# Sheet5.net
KiCad netlist of a schematic drawn in Altium Designer
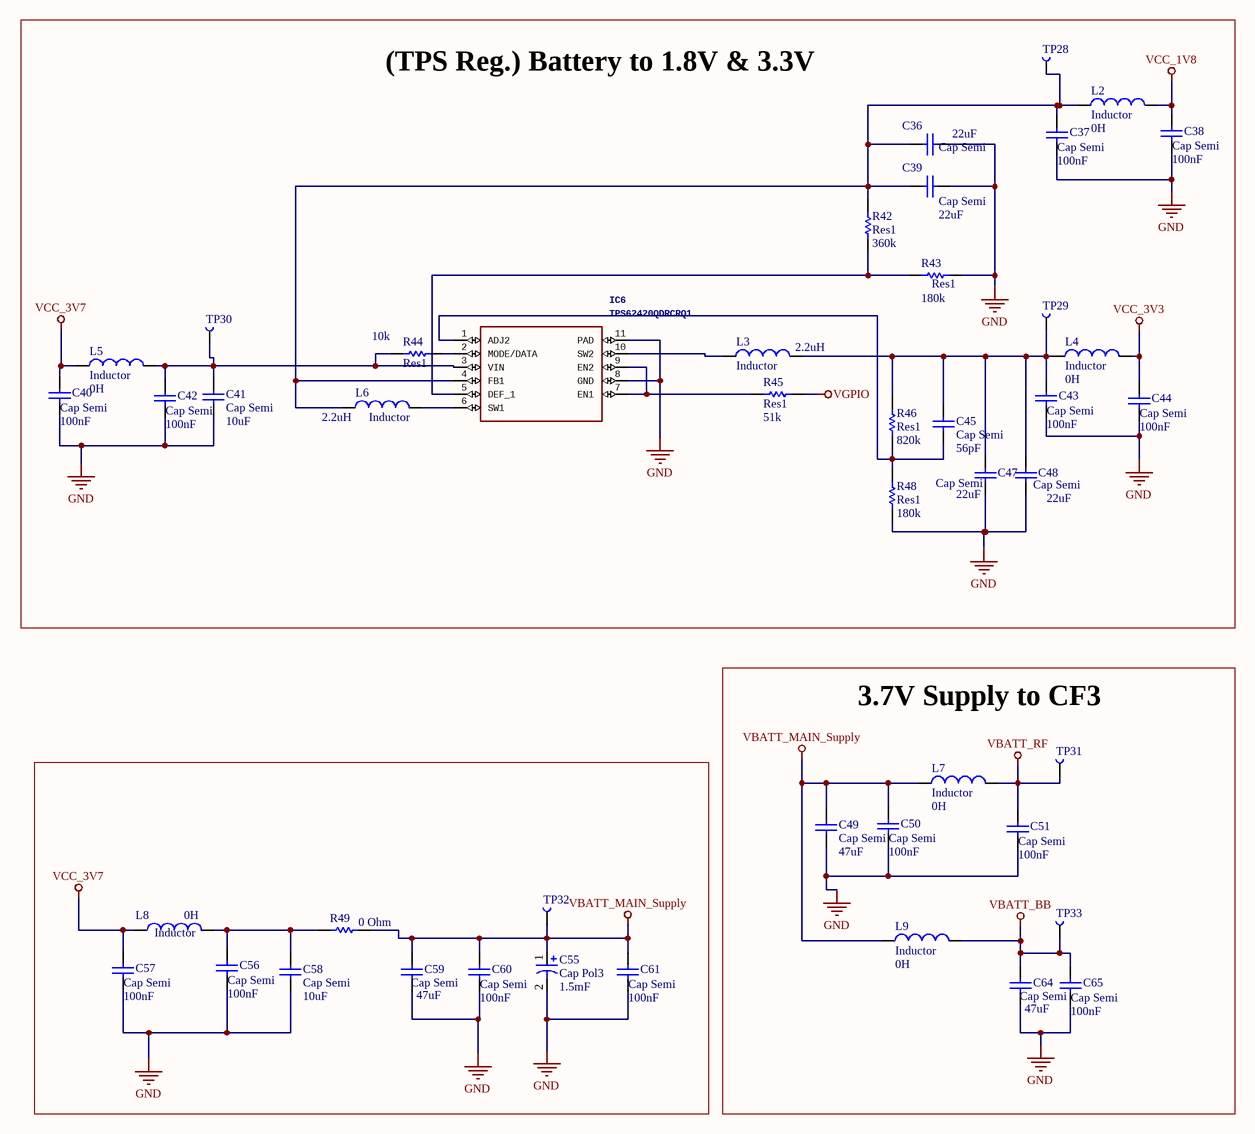
[diagram p0: Sheet5.SchDoc]

(export (version "E")
  (design (tool "Eeschema 10.0.6"))
  (components
    (comp (ref "C36")
      (value "Cap Semi")
      (footprint "CAP 0603/1608")
      (description "22µF ±20% 6.3V Ceramic Capacitor X5R 0603 (1608 Metric)")
      (fields
        (field (name "PART NUMBER") "GRM188R60J226MEA0D")
        (field (name "ALTIUM_VALUE") "22uF")
        (field (name "PUBLISHER") "Altium Limited")
      )
      (libsource (lib "Miscellaneous Devices") (part "Cap Semi"))
    )
    (comp (ref "C37")
      (value "Cap Semi")
      (footprint "CAP 0402/1005")
      (description "0.1µF ±10% 10V Ceramic Capacitor X5R 0402 (1005 Metric)")
      (fields (field (name "PART NUMBER") "LMK105BJ104KV-F") (field (name "ALTIUM_VALUE") "100nF"))
      (libsource (lib "Miscellaneous Devices") (part "Cap Semi"))
    )
    (comp (ref "C38")
      (value "Cap Semi")
      (footprint "CAP 0402/1005")
      (description "0.1µF ±10% 10V Ceramic Capacitor X5R 0402 (1005 Metric)")
      (fields (field (name "PART NUMBER") "LMK105BJ104KV-F") (field (name "ALTIUM_VALUE") "100nF"))
      (libsource (lib "Miscellaneous Devices") (part "Cap Semi"))
    )
    (comp (ref "C39")
      (value "Cap Semi")
      (footprint "CAP 0603/1608")
      (description "22µF ±20% 6.3V Ceramic Capacitor X5R 0603 (1608 Metric)")
      (fields
        (field (name "PART NUMBER") "GRM188R60J226MEA0D")
        (field (name "ALTIUM_VALUE") "22uF")
        (field (name "PUBLISHER") "Altium Limited")
      )
      (libsource (lib "Miscellaneous Devices") (part "Cap Semi"))
    )
    (comp (ref "C40")
      (value "Cap Semi")
      (footprint "CAP 0402/1005")
      (description "0.1µF -20%, +80% 16V Ceramic Capacitor Y5V (F) 0402 (1005 Metric)")
      (fields (field (name "PART NUMBER") "VJ0402V104ZXJCW1BC") (field (name "ALTIUM_VALUE") "100nF"))
      (libsource (lib "Miscellaneous Devices") (part "Cap Semi"))
    )
    (comp (ref "C41")
      (value "Cap Semi")
      (footprint "CAP 0805/2012")
      (description "10µF ±10% 10V Ceramic Capacitor X5R 0805 (2012 Metric)")
      (fields
        (field (name "PART NUMBER") "LMK212BJ106KG-T")
        (field (name "ALTIUM_VALUE") "10uF")
        (field (name "PUBLISHER") "Altium Limited")
      )
      (libsource (lib "Miscellaneous Devices") (part "Cap Semi"))
    )
    (comp (ref "C42")
      (value "Cap Semi")
      (footprint "CAP 0402/1005")
      (description "0.1µF -20%, +80% 16V Ceramic Capacitor Y5V (F) 0402 (1005 Metric)")
      (fields (field (name "PART NUMBER") "VJ0402V104ZXJCW1BC") (field (name "ALTIUM_VALUE") "100nF"))
      (libsource (lib "Miscellaneous Devices") (part "Cap Semi"))
    )
    (comp (ref "C43")
      (value "Cap Semi")
      (footprint "CAP 0402/1005")
      (description "0.1µF ±10% 10V Ceramic Capacitor X5R 0402 (1005 Metric)")
      (fields (field (name "PART NUMBER") "LMK105BJ104KV-F") (field (name "ALTIUM_VALUE") "100nF"))
      (libsource (lib "Miscellaneous Devices") (part "Cap Semi"))
    )
    (comp (ref "C44")
      (value "Cap Semi")
      (footprint "CAP 0402/1005")
      (description "0.1µF ±10% 10V Ceramic Capacitor X5R 0402 (1005 Metric)")
      (fields (field (name "PART NUMBER") "LMK105BJ104KV-F") (field (name "ALTIUM_VALUE") "100nF"))
      (libsource (lib "Miscellaneous Devices") (part "Cap Semi"))
    )
    (comp (ref "C45")
      (value "Cap Semi")
      (footprint "CAP 0402/1005")
      (description "56pF ±5% 50V Ceramic Capacitor C0G, NP0 0402 (1005 Metric)")
      (fields
        (field (name "PART NUMBER") "UMK105CG560JV-F")
        (field (name "ALTIUM_VALUE") "56pF")
        (field (name "PUBLISHER") "Altium Limited")
      )
      (libsource (lib "Miscellaneous Devices") (part "Cap Semi"))
    )
    (comp (ref "C47")
      (value "Cap Semi")
      (footprint "CAP 0603/1608")
      (description "22µF ±20% 6.3V Ceramic Capacitor X5R 0603 (1608 Metric)")
      (fields
        (field (name "PART NUMBER") "GRM188R60J226MEA0D")
        (field (name "ALTIUM_VALUE") "22uF")
        (field (name "PUBLISHER") "Altium Limited")
      )
      (libsource (lib "Miscellaneous Devices") (part "Cap Semi"))
    )
    (comp (ref "C48")
      (value "Cap Semi")
      (footprint "CAP 0603/1608")
      (description "22µF ±20% 6.3V Ceramic Capacitor X5R 0603 (1608 Metric)")
      (fields
        (field (name "PART NUMBER") "GRM188R60J226MEA0D")
        (field (name "ALTIUM_VALUE") "22uF")
        (field (name "PUBLISHER") "Altium Limited")
      )
      (libsource (lib "Miscellaneous Devices") (part "Cap Semi"))
    )
    (comp (ref "C49")
      (value "Cap Semi")
      (footprint "CAP 1206/3216")
      (description "47µF ±20% 10V Ceramic Capacitor X5R 1206 (3216 Metric)")
      (fields
        (field (name "PART NUMBER") "LMK316BJ476ML-T")
        (field (name "ALTIUM_VALUE") "47uF")
        (field (name "PUBLISHER") "Altium Limited")
      )
      (libsource (lib "Miscellaneous Devices") (part "Cap Semi"))
    )
    (comp (ref "C50")
      (value "Cap Semi")
      (footprint "CAP 0402/1005")
      (description "0.1µF ±10% 10V Ceramic Capacitor X5R 0402 (1005 Metric)")
      (fields (field (name "PART NUMBER") "LMK105BJ104KV-F") (field (name "ALTIUM_VALUE") "100nF"))
      (libsource (lib "Miscellaneous Devices") (part "Cap Semi"))
    )
    (comp (ref "C51")
      (value "Cap Semi")
      (footprint "CAP 0402/1005")
      (description "0.1µF ±10% 10V Ceramic Capacitor X5R 0402 (1005 Metric)")
      (fields (field (name "PART NUMBER") "LMK105BJ104KV-F") (field (name "ALTIUM_VALUE") "100nF"))
      (libsource (lib "Miscellaneous Devices") (part "Cap Semi"))
    )
    (comp (ref "C55")
      (value "Cap Pol3")
      (footprint "F720J158MMC")
      (description "1500µF Conformal Coated Tantalum Capacitors 6.3V 2824 (7260 Metric) 140 mOhm")
      (fields
        (field (name "ALTIUM_VALUE") "1.5mF")
        (field (name "PART NUMBER") "F720J158MMC")
        (field (name "PUBLISHER") "Altium Limited")
      )
      (libsource (lib "Miscellaneous Devices") (part "Cap Pol3"))
    )
    (comp (ref "C56")
      (value "Cap Semi")
      (footprint "CAP 0402/1005")
      (description "0.1µF -20%, +80% 16V Ceramic Capacitor Y5V (F) 0402 (1005 Metric)")
      (fields (field (name "PART NUMBER") "VJ0402V104ZXJCW1BC") (field (name "ALTIUM_VALUE") "100nF"))
      (libsource (lib "Miscellaneous Devices") (part "Cap Semi"))
    )
    (comp (ref "C57")
      (value "Cap Semi")
      (footprint "CAP 0402/1005")
      (description "0.1µF -20%, +80% 16V Ceramic Capacitor Y5V (F) 0402 (1005 Metric)")
      (fields (field (name "PART NUMBER") "VJ0402V104ZXJCW1BC") (field (name "ALTIUM_VALUE") "100nF"))
      (libsource (lib "Miscellaneous Devices") (part "Cap Semi"))
    )
    (comp (ref "C58")
      (value "Cap Semi")
      (footprint "CAP 0603/1608")
      (description "10µF ±20% 10V Ceramic Capacitor X5R 0603 (1608 Metric)")
      (fields
        (field (name "PART NUMBER") "GRM188R61A106ME69D")
        (field (name "ALTIUM_VALUE") "10uF")
        (field (name "PUBLISHER") "Altium Limited")
      )
      (libsource (lib "Miscellaneous Devices") (part "Cap Semi"))
    )
    (comp (ref "C59")
      (value "Cap Semi")
      (footprint "CAP 1206/3216")
      (description "47µF ±20% 10V Ceramic Capacitor X5R 1206 (3216 Metric)")
      (fields
        (field (name "PART NUMBER") "LMK316BJ476ML-T")
        (field (name "ALTIUM_VALUE") "47uF")
        (field (name "PUBLISHER") "Altium Limited")
      )
      (libsource (lib "Miscellaneous Devices") (part "Cap Semi"))
    )
    (comp (ref "C60")
      (value "Cap Semi")
      (footprint "CAP 0402/1005")
      (description "0.1µF ±10% 10V Ceramic Capacitor X5R 0402 (1005 Metric)")
      (fields (field (name "PART NUMBER") "LMK105BJ104KV-F") (field (name "ALTIUM_VALUE") "100nF"))
      (libsource (lib "Miscellaneous Devices") (part "Cap Semi"))
    )
    (comp (ref "C61")
      (value "Cap Semi")
      (footprint "CAP 0402/1005")
      (description "0.1µF ±10% 10V Ceramic Capacitor X5R 0402 (1005 Metric)")
      (fields (field (name "PART NUMBER") "LMK105BJ104KV-F") (field (name "ALTIUM_VALUE") "100nF"))
      (libsource (lib "Miscellaneous Devices") (part "Cap Semi"))
    )
    (comp (ref "C64")
      (value "Cap Semi")
      (footprint "CAP 1206/3216")
      (description "47µF ±20% 10V Ceramic Capacitor X5R 1206 (3216 Metric)")
      (fields
        (field (name "PART NUMBER") "LMK316BJ476ML-T")
        (field (name "ALTIUM_VALUE") "47uF")
        (field (name "PUBLISHER") "Altium Limited")
      )
      (libsource (lib "Miscellaneous Devices") (part "Cap Semi"))
    )
    (comp (ref "C65")
      (value "Cap Semi")
      (footprint "CAP 0402/1005")
      (description "0.1µF ±10% 10V Ceramic Capacitor X5R 0402 (1005 Metric)")
      (fields (field (name "PART NUMBER") "LMK105BJ104KV-F") (field (name "ALTIUM_VALUE") "100nF"))
      (libsource (lib "Miscellaneous Devices") (part "Cap Semi"))
    )
    (comp (ref "IC6")
      (value "TPS62420QDRCRQ1")
      (footprint "SON50P300X300X100-11N - 3D")
      (description "Buck Switching Regulator IC Positive Adjustable 0.6V 2 Output 600mA, 1A 10-VFDFN Exposed Pad")
      (fields (field (name "PART NUMBER") "TPS62420DRCR"))
      (libsource (lib "TPS62420QDRCRQ1") (part "TPS62420QDRCRQ1"))
    )
    (comp (ref "L2")
      (value "Inductor")
      (footprint "INDC1608L")
      (description "220 Ohms @ 100MHz 1 Power Line Ferrite Bead 0603 (1608 Metric) 2.2A 50 mOhm")
      (fields
        (field (name "ALTIUM_VALUE") "0H")
        (field (name "PART NUMBER") "MPZ1608S221ATA00")
        (field (name "PUBLISHER") "Altium Limited")
      )
      (libsource (lib "Miscellaneous Devices") (part "Inductor"))
    )
    (comp (ref "L3")
      (value "Inductor")
      (footprint "0402-A")
      (fields
        (field (name "ALTIUM_VALUE") "2.2uH")
        (field (name "PART NUMBER") "MIPF2016D2R2")
        (field (name "PUBLISHER") "Altium Limited")
      )
      (libsource (lib "Miscellaneous Devices") (part "Inductor"))
    )
    (comp (ref "L4")
      (value "Inductor")
      (footprint "INDC1608L")
      (description "220 Ohms @ 100MHz 1 Power Line Ferrite Bead 0603 (1608 Metric) 2.2A 50 mOhm")
      (fields
        (field (name "ALTIUM_VALUE") "0H")
        (field (name "PART NUMBER") "MPZ1608S221ATA00")
        (field (name "PUBLISHER") "Altium Limited")
      )
      (libsource (lib "Miscellaneous Devices") (part "Inductor"))
    )
    (comp (ref "L5")
      (value "Inductor")
      (footprint "INDC1608L")
      (description "220 Ohms @ 100MHz 1 Power Line Ferrite Bead 0603 (1608 Metric) 2.2A 50 mOhm")
      (fields
        (field (name "ALTIUM_VALUE") "0H")
        (field (name "PART NUMBER") "MPZ1608S221ATA00")
        (field (name "PUBLISHER") "Altium Limited")
      )
      (libsource (lib "Miscellaneous Devices") (part "Inductor"))
    )
    (comp (ref "L6")
      (value "Inductor")
      (footprint "0402-A")
      (fields
        (field (name "ALTIUM_VALUE") "2.2uH")
        (field (name "PART NUMBER") "MIPF2016D2R2")
        (field (name "PUBLISHER") "Altium Limited")
      )
      (libsource (lib "Miscellaneous Devices") (part "Inductor"))
    )
    (comp (ref "L7")
      (value "Inductor")
      (footprint "INDC1608L")
      (description "120 Ohms @ 100MHz 1 Power Line Ferrite Bead 0603 (1608 Metric) 2.7A 35 mOhm")
      (fields
        (field (name "ALTIUM_VALUE") "0H")
        (field (name "PART NUMBER") "BKP1608HS121-T")
        (field (name "PUBLISHER") "Altium Limited")
      )
      (libsource (lib "Miscellaneous Devices") (part "Inductor"))
    )
    (comp (ref "L8")
      (value "Inductor")
      (footprint "INDC1608L")
      (description "120 Ohms @ 100MHz 1 Power Line Ferrite Bead 0603 (1608 Metric) 2.7A 35 mOhm")
      (fields
        (field (name "ALTIUM_VALUE") "0H")
        (field (name "PART NUMBER") "BKP1608HS121-T")
        (field (name "PUBLISHER") "Altium Limited")
      )
      (libsource (lib "Miscellaneous Devices") (part "Inductor"))
    )
    (comp (ref "L9")
      (value "Inductor")
      (footprint "INDC1608L")
      (description "120 Ohms @ 100MHz 1 Power Line Ferrite Bead 0603 (1608 Metric) 2.7A 35 mOhm")
      (fields
        (field (name "ALTIUM_VALUE") "0H")
        (field (name "PART NUMBER") "BKP1608HS121-T")
        (field (name "PUBLISHER") "Altium Limited")
      )
      (libsource (lib "Miscellaneous Devices") (part "Inductor"))
    )
    (comp (ref "R42")
      (value "Res1")
      (footprint "RES 0402/1005")
      (description "360 kOhms ±1% 0.063W, 1/16W Chip Resistor 0402 (1005 Metric) Automotive AEC-Q200 Thick Film")
      (fields (field (name "PART NUMBER") "MCR01MZPF3603") (field (name "ALTIUM_VALUE") "360k"))
      (libsource (lib "Miscellaneous Devices") (part "Res1"))
    )
    (comp (ref "R43")
      (value "Res1")
      (footprint "RES 0402/1005")
      (description "180 kOhms ±1% 0.1W, 1/10W Chip Resistor 0402 (1005 Metric) Automotive AEC-Q200 Thick Film")
      (fields (field (name "PART NUMBER") "RK73H1ETTP1803F") (field (name "ALTIUM_VALUE") "180k"))
      (libsource (lib "Miscellaneous Devices") (part "Res1"))
    )
    (comp (ref "R44")
      (value "Res1")
      (footprint "RES 0402/1005")
      (description "10 kOhms ±5% 0.063W, 1/16W Chip Resistor 0402 (1005 Metric) Automotive AEC-Q200 Thick Film")
      (fields (field (name "PART NUMBER") "MCR01MZPJ103") (field (name "ALTIUM_VALUE") "10k"))
      (libsource (lib "Miscellaneous Devices") (part "Res1"))
    )
    (comp (ref "R45")
      (value "Res1")
      (footprint "RES 0402/1005")
      (description "51 kOhms ±5% 0.063W, 1/16W Chip Resistor 0402 (1005 Metric)")
      (fields (field (name "PART NUMBER") "MCR01MZPJ513") (field (name "ALTIUM_VALUE") "51k"))
      (libsource (lib "Miscellaneous Devices") (part "Res1"))
    )
    (comp (ref "R46")
      (value "Res1")
      (footprint "RES 0402/1005")
      (description "820 kOhms ±1% 0.063W, 1/16W Chip Resistor 0402 (1005 Metric) Moisture Resistant Thick Film")
      (fields (field (name "PART NUMBER") "RC0402FR-07820KL") (field (name "ALTIUM_VALUE") "820k"))
      (libsource (lib "Miscellaneous Devices") (part "Res1"))
    )
    (comp (ref "R48")
      (value "Res1")
      (footprint "RES 0402/1005")
      (description "180 kOhms ±1% 0.1W, 1/10W Chip Resistor 0402 (1005 Metric) Automotive AEC-Q200 Thick Film")
      (fields (field (name "PART NUMBER") "RK73H1ETTP1803F") (field (name "ALTIUM_VALUE") "180k"))
      (libsource (lib "Miscellaneous Devices") (part "Res1"))
    )
    (comp (ref "R49")
      (value "0 Ohm")
      (footprint "RES 0402/1005")
      (description "0 Ohms Jumper  Chip Resistor 0402 (1005 Metric) Automotive AEC-Q200 Metal Element")
      (fields (field (name "PART NUMBER") "RK73Z1ETTP") (field (name "Comment") "Res1"))
      (libsource (lib "Miscellaneous Devices") (part "Res1"))
    )
    (comp (ref "TP28")
      (value "TestPoint")
      (footprint "TestPoint")
      (libsource (lib "TestPoint") (part "TestPoint"))
    )
    (comp (ref "TP29")
      (value "TestPoint")
      (footprint "TestPoint")
      (libsource (lib "TestPoint") (part "TestPoint"))
    )
    (comp (ref "TP30")
      (value "TestPoint")
      (footprint "TestPoint")
      (libsource (lib "TestPoint") (part "TestPoint"))
    )
    (comp (ref "TP31")
      (value "TestPoint")
      (footprint "TestPoint")
      (libsource (lib "TestPoint") (part "TestPoint"))
    )
    (comp (ref "TP32")
      (value "TestPoint")
      (footprint "TestPoint")
      (libsource (lib "TestPoint") (part "TestPoint"))
    )
    (comp (ref "TP33")
      (value "TestPoint")
      (footprint "TestPoint")
      (libsource (lib "TestPoint") (part "TestPoint"))
    )
  )
  (nets
    (net (code "1") (name "GND") (class "Default")
      (node (ref "C36") (pin "1") (pinfunction "1_1") (pintype "passive"))
      (node (ref "C37") (pin "1") (pinfunction "1_1") (pintype "passive"))
      (node (ref "C38") (pin "1") (pinfunction "1_1") (pintype "passive"))
      (node (ref "C39") (pin "1") (pinfunction "1_1") (pintype "passive"))
      (node (ref "C40") (pin "1") (pinfunction "1_1") (pintype "passive"))
      (node (ref "C41") (pin "1") (pinfunction "1_1") (pintype "passive"))
      (node (ref "C42") (pin "1") (pinfunction "1_1") (pintype "passive"))
      (node (ref "C43") (pin "1") (pinfunction "1_1") (pintype "passive"))
      (node (ref "C44") (pin "1") (pinfunction "1_1") (pintype "passive"))
      (node (ref "C47") (pin "1") (pinfunction "1_1") (pintype "passive"))
      (node (ref "C48") (pin "1") (pinfunction "1_1") (pintype "passive"))
      (node (ref "C49") (pin "1") (pinfunction "1_1") (pintype "passive"))
      (node (ref "C50") (pin "1") (pinfunction "1_1") (pintype "passive"))
      (node (ref "C51") (pin "1") (pinfunction "1_1") (pintype "passive"))
      (node (ref "C55") (pin "2") (pinfunction "2_2") (pintype "passive"))
      (node (ref "C56") (pin "1") (pinfunction "1_1") (pintype "passive"))
      (node (ref "C57") (pin "1") (pinfunction "1_1") (pintype "passive"))
      (node (ref "C58") (pin "1") (pinfunction "1_1") (pintype "passive"))
      (node (ref "C59") (pin "1") (pinfunction "1_1") (pintype "passive"))
      (node (ref "C60") (pin "1") (pinfunction "1_1") (pintype "passive"))
      (node (ref "C61") (pin "1") (pinfunction "1_1") (pintype "passive"))
      (node (ref "C64") (pin "1") (pinfunction "1_1") (pintype "passive"))
      (node (ref "C65") (pin "1") (pinfunction "1_1") (pintype "passive"))
      (node (ref "IC6") (pin "11") (pinfunction "PAD_11") (pintype "bidirectional"))
      (node (ref "IC6") (pin "8") (pinfunction "GND_8") (pintype "bidirectional"))
      (node (ref "R43") (pin "1") (pinfunction "1_1") (pintype "passive"))
      (node (ref "R48") (pin "1") (pinfunction "1_1") (pintype "passive"))
    )
    (net (code "2") (name "Net-(C56-Pad2)") (class "Default")
      (node (ref "C56") (pin "2") (pinfunction "2_2") (pintype "passive"))
      (node (ref "C58") (pin "2") (pinfunction "2_2") (pintype "passive"))
      (node (ref "L8") (pin "2") (pinfunction "2_2") (pintype "passive"))
      (node (ref "R49") (pin "1") (pinfunction "1_1") (pintype "passive"))
    )
    (net (code "3") (name "Net-(IC6-ADJ2)") (class "Default")
      (node (ref "C45") (pin "1") (pinfunction "1_1") (pintype "passive"))
      (node (ref "IC6") (pin "1") (pinfunction "ADJ2_1") (pintype "bidirectional"))
      (node (ref "R46") (pin "1") (pinfunction "1_1") (pintype "passive"))
      (node (ref "R48") (pin "2") (pinfunction "2_2") (pintype "passive"))
    )
    (net (code "4") (name "Net-(IC6-DEF_1)") (class "Default")
      (node (ref "IC6") (pin "5") (pinfunction "DEF_1_5") (pintype "bidirectional"))
      (node (ref "R42") (pin "2") (pinfunction "2_2") (pintype "passive"))
      (node (ref "R43") (pin "2") (pinfunction "2_2") (pintype "passive"))
    )
    (net (code "5") (name "Net-(IC6-EN1)") (class "Default")
      (node (ref "IC6") (pin "7") (pinfunction "EN1_7") (pintype "bidirectional"))
      (node (ref "IC6") (pin "9") (pinfunction "EN2_9") (pintype "bidirectional"))
      (node (ref "R45") (pin "1") (pinfunction "1_1") (pintype "passive"))
    )
    (net (code "6") (name "Net-(IC6-FB1)") (class "Default")
      (node (ref "C36") (pin "2") (pinfunction "2_2") (pintype "passive"))
      (node (ref "C37") (pin "2") (pinfunction "2_2") (pintype "passive"))
      (node (ref "C39") (pin "2") (pinfunction "2_2") (pintype "passive"))
      (node (ref "IC6") (pin "4") (pinfunction "FB1_4") (pintype "bidirectional"))
      (node (ref "L2") (pin "1") (pinfunction "1_1") (pintype "passive"))
      (node (ref "L6") (pin "1") (pinfunction "1_1") (pintype "passive"))
      (node (ref "R42") (pin "1") (pinfunction "1_1") (pintype "passive"))
      (node (ref "TP28") (pin "1") (pinfunction "TP_1") (pintype "passive"))
    )
    (net (code "7") (name "Net-(IC6-MODE{slash}DATA)") (class "Default")
      (node (ref "IC6") (pin "2") (pinfunction "MODE/DATA_2") (pintype "bidirectional"))
      (node (ref "R44") (pin "2") (pinfunction "2_2") (pintype "passive"))
    )
    (net (code "8") (name "Net-(IC6-SW1)") (class "Default")
      (node (ref "IC6") (pin "6") (pinfunction "SW1_6") (pintype "bidirectional"))
      (node (ref "L6") (pin "2") (pinfunction "2_2") (pintype "passive"))
    )
    (net (code "9") (name "Net-(IC6-SW2)") (class "Default")
      (node (ref "IC6") (pin "10") (pinfunction "SW2_10") (pintype "bidirectional"))
      (node (ref "L3") (pin "1") (pinfunction "1_1") (pintype "passive"))
    )
    (net (code "10") (name "Net-(IC6-VIN)") (class "Default")
      (node (ref "C41") (pin "2") (pinfunction "2_2") (pintype "passive"))
      (node (ref "C42") (pin "2") (pinfunction "2_2") (pintype "passive"))
      (node (ref "IC6") (pin "3") (pinfunction "VIN_3") (pintype "bidirectional"))
      (node (ref "L5") (pin "2") (pinfunction "2_2") (pintype "passive"))
      (node (ref "R44") (pin "1") (pinfunction "1_1") (pintype "passive"))
      (node (ref "TP30") (pin "1") (pinfunction "TP_1") (pintype "passive"))
    )
    (net (code "11") (name "Net-(TP29-TP)") (class "Default")
      (node (ref "C43") (pin "2") (pinfunction "2_2") (pintype "passive"))
      (node (ref "C45") (pin "2") (pinfunction "2_2") (pintype "passive"))
      (node (ref "C47") (pin "2") (pinfunction "2_2") (pintype "passive"))
      (node (ref "C48") (pin "2") (pinfunction "2_2") (pintype "passive"))
      (node (ref "L3") (pin "2") (pinfunction "2_2") (pintype "passive"))
      (node (ref "L4") (pin "1") (pinfunction "1_1") (pintype "passive"))
      (node (ref "R46") (pin "2") (pinfunction "2_2") (pintype "passive"))
      (node (ref "TP29") (pin "1") (pinfunction "TP_1") (pintype "passive"))
    )
    (net (code "12") (name "VBATT_BB") (class "Default")
      (node (ref "C64") (pin "2") (pinfunction "2_2") (pintype "passive"))
      (node (ref "C65") (pin "2") (pinfunction "2_2") (pintype "passive"))
      (node (ref "L9") (pin "2") (pinfunction "2_2") (pintype "passive"))
      (node (ref "TP33") (pin "1") (pinfunction "TP_1") (pintype "passive"))
    )
    (net (code "13") (name "VBATT_MAIN_Supply") (class "Default")
      (node (ref "C49") (pin "2") (pinfunction "2_2") (pintype "passive"))
      (node (ref "C50") (pin "2") (pinfunction "2_2") (pintype "passive"))
      (node (ref "C55") (pin "1") (pinfunction "1_1") (pintype "passive"))
      (node (ref "C59") (pin "2") (pinfunction "2_2") (pintype "passive"))
      (node (ref "C60") (pin "2") (pinfunction "2_2") (pintype "passive"))
      (node (ref "C61") (pin "2") (pinfunction "2_2") (pintype "passive"))
      (node (ref "L7") (pin "1") (pinfunction "1_1") (pintype "passive"))
      (node (ref "L9") (pin "1") (pinfunction "1_1") (pintype "passive"))
      (node (ref "R49") (pin "2") (pinfunction "2_2") (pintype "passive"))
      (node (ref "TP32") (pin "1") (pinfunction "TP_1") (pintype "passive"))
    )
    (net (code "14") (name "VBATT_RF") (class "Default")
      (node (ref "C51") (pin "2") (pinfunction "2_2") (pintype "passive"))
      (node (ref "L7") (pin "2") (pinfunction "2_2") (pintype "passive"))
      (node (ref "TP31") (pin "1") (pinfunction "TP_1") (pintype "passive"))
    )
    (net (code "15") (name "VCC_1V8") (class "Default")
      (node (ref "C38") (pin "2") (pinfunction "2_2") (pintype "passive"))
      (node (ref "L2") (pin "2") (pinfunction "2_2") (pintype "passive"))
    )
    (net (code "16") (name "VCC_3V3") (class "Default")
      (node (ref "C44") (pin "2") (pinfunction "2_2") (pintype "passive"))
      (node (ref "L4") (pin "2") (pinfunction "2_2") (pintype "passive"))
    )
    (net (code "17") (name "VCC_3V7") (class "Default")
      (node (ref "C40") (pin "2") (pinfunction "2_2") (pintype "passive"))
      (node (ref "C57") (pin "2") (pinfunction "2_2") (pintype "passive"))
      (node (ref "L5") (pin "1") (pinfunction "1_1") (pintype "passive"))
      (node (ref "L8") (pin "1") (pinfunction "1_1") (pintype "passive"))
    )
    (net (code "18") (name "VGPIO") (class "Default")
      (node (ref "R45") (pin "2") (pinfunction "2_2") (pintype "passive"))
    )
  )
)
